# nfr24l_module.net
KiCad netlist of a schematic drawn in EAGLE
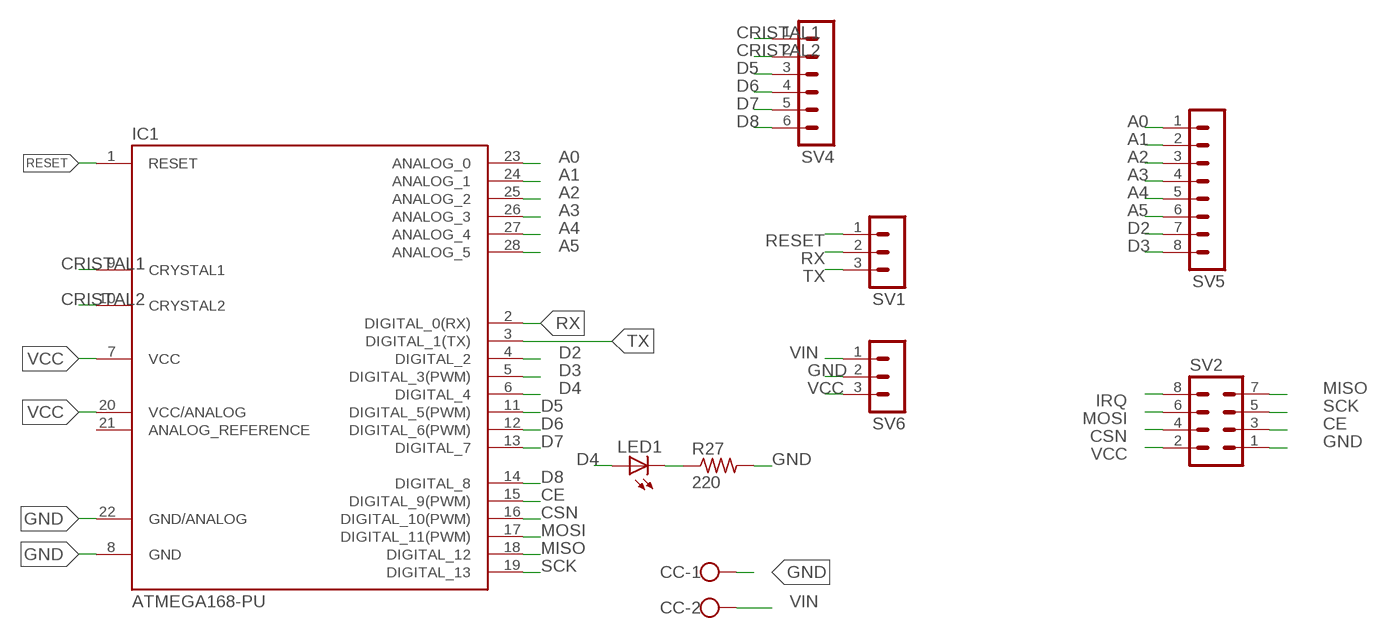
[diagram p0: schematic, sheet 1]

(export (version "E")
  (design (tool "Eeschema 10.0.6"))
  (components
    (comp (ref "CC")
      (value "W237-102")
      (footprint "eagle-import:W237-102")
      (fields (field (name "MPN") "237-102"))
      (libsource (lib "eagle-import") (part "W237-102"))
    )
    (comp (ref "IC1")
      (value "ATMEGA168-PU")
      (footprint "eagle-import:DIL28-3")
      (libsource (lib "eagle-import") (part "ATMEGA168-PU"))
    )
    (comp (ref "LED1")
      (value "LED3MM")
      (footprint "eagle-import:LED3MM")
      (libsource (lib "eagle-import") (part "LED3MM"))
    )
    (comp (ref "R27")
      (value "220")
      (footprint "eagle-import:0207_7")
      (libsource (lib "eagle-import") (part "R-US_0207/7"))
    )
    (comp (ref "SV1")
      (value "MA03-1")
      (footprint "eagle-import:MA03-1")
      (libsource (lib "eagle-import") (part "MA03-1"))
    )
    (comp (ref "SV2")
      (value "MA04-2")
      (footprint "eagle-import:MA04-2")
      (libsource (lib "eagle-import") (part "MA04-2"))
    )
    (comp (ref "SV4")
      (value "MA06-1")
      (footprint "eagle-import:MA06-1")
      (libsource (lib "eagle-import") (part "MA06-1"))
    )
    (comp (ref "SV5")
      (value "MA08-1")
      (footprint "eagle-import:MA08-1")
      (libsource (lib "eagle-import") (part "MA08-1"))
    )
    (comp (ref "SV6")
      (value "MA03-1")
      (footprint "eagle-import:MA03-1")
      (libsource (lib "eagle-import") (part "MA03-1"))
    )
  )
  (nets
    (net (code "1") (name "/A0") (class "Default")
      (node (ref "IC1") (pin "23") (pinfunction "ANALOG_0_23") (pintype "bidirectional"))
      (node (ref "SV5") (pin "1") (pinfunction "1_1") (pintype "passive"))
    )
    (net (code "2") (name "/A1") (class "Default")
      (node (ref "IC1") (pin "24") (pinfunction "ANALOG_1_24") (pintype "bidirectional"))
      (node (ref "SV5") (pin "2") (pinfunction "2_2") (pintype "passive"))
    )
    (net (code "3") (name "/A2") (class "Default")
      (node (ref "IC1") (pin "25") (pinfunction "ANALOG_2_25") (pintype "bidirectional"))
      (node (ref "SV5") (pin "3") (pinfunction "3_3") (pintype "passive"))
    )
    (net (code "4") (name "/A3") (class "Default")
      (node (ref "IC1") (pin "26") (pinfunction "ANALOG_3_26") (pintype "bidirectional"))
      (node (ref "SV5") (pin "4") (pinfunction "4_4") (pintype "passive"))
    )
    (net (code "5") (name "/A4") (class "Default")
      (node (ref "IC1") (pin "27") (pinfunction "ANALOG_4_27") (pintype "bidirectional"))
      (node (ref "SV5") (pin "5") (pinfunction "5_5") (pintype "passive"))
    )
    (net (code "6") (name "/A5") (class "Default")
      (node (ref "IC1") (pin "28") (pinfunction "ANALOG_5_28") (pintype "bidirectional"))
      (node (ref "SV5") (pin "6") (pinfunction "6_6") (pintype "passive"))
    )
    (net (code "7") (name "/CE") (class "Default")
      (node (ref "IC1") (pin "15") (pinfunction "DIGITAL_9(PWM)_15") (pintype "bidirectional"))
      (node (ref "SV2") (pin "3") (pinfunction "3_3") (pintype "passive"))
    )
    (net (code "8") (name "/CRISTAL1") (class "Default")
      (node (ref "IC1") (pin "9") (pinfunction "CRYSTAL1_9") (pintype "bidirectional"))
      (node (ref "SV4") (pin "1") (pinfunction "1_1") (pintype "passive"))
    )
    (net (code "9") (name "/CRISTAL2") (class "Default")
      (node (ref "IC1") (pin "10") (pinfunction "CRYSTAL2_10") (pintype "bidirectional"))
      (node (ref "SV4") (pin "2") (pinfunction "2_2") (pintype "passive"))
    )
    (net (code "10") (name "/CSN") (class "Default")
      (node (ref "IC1") (pin "16") (pinfunction "DIGITAL_10(PWM)_16") (pintype "bidirectional"))
      (node (ref "SV2") (pin "4") (pinfunction "4_4") (pintype "passive"))
    )
    (net (code "11") (name "/D2") (class "Default")
      (node (ref "IC1") (pin "4") (pinfunction "DIGITAL_2_4") (pintype "bidirectional"))
      (node (ref "SV5") (pin "7") (pinfunction "7_7") (pintype "passive"))
    )
    (net (code "12") (name "/D3") (class "Default")
      (node (ref "IC1") (pin "5") (pinfunction "DIGITAL_3(PWM)_5") (pintype "bidirectional"))
      (node (ref "SV5") (pin "8") (pinfunction "8_8") (pintype "passive"))
    )
    (net (code "13") (name "/D4") (class "Default")
      (node (ref "IC1") (pin "6") (pinfunction "DIGITAL_4_6") (pintype "bidirectional"))
      (node (ref "LED1") (pin "A") (pinfunction "A_A") (pintype "passive"))
    )
    (net (code "14") (name "/D5") (class "Default")
      (node (ref "IC1") (pin "11") (pinfunction "DIGITAL_5(PWM)_11") (pintype "bidirectional"))
      (node (ref "SV4") (pin "3") (pinfunction "3_3") (pintype "passive"))
    )
    (net (code "15") (name "/D6") (class "Default")
      (node (ref "IC1") (pin "12") (pinfunction "DIGITAL_6(PWM)_12") (pintype "bidirectional"))
      (node (ref "SV4") (pin "4") (pinfunction "4_4") (pintype "passive"))
    )
    (net (code "16") (name "/D7") (class "Default")
      (node (ref "IC1") (pin "13") (pinfunction "DIGITAL_7_13") (pintype "bidirectional"))
      (node (ref "SV4") (pin "5") (pinfunction "5_5") (pintype "passive"))
    )
    (net (code "17") (name "/D8") (class "Default")
      (node (ref "IC1") (pin "14") (pinfunction "DIGITAL_8_14") (pintype "bidirectional"))
      (node (ref "SV4") (pin "6") (pinfunction "6_6") (pintype "passive"))
    )
    (net (code "18") (name "/IRQ") (class "Default")
      (node (ref "SV2") (pin "8") (pinfunction "8_8") (pintype "passive"))
    )
    (net (code "19") (name "/MISO") (class "Default")
      (node (ref "IC1") (pin "18") (pinfunction "DIGITAL_12_18") (pintype "bidirectional"))
      (node (ref "SV2") (pin "7") (pinfunction "7_7") (pintype "passive"))
    )
    (net (code "20") (name "/MOSI") (class "Default")
      (node (ref "IC1") (pin "17") (pinfunction "DIGITAL_11(PWM)_17") (pintype "bidirectional"))
      (node (ref "SV2") (pin "6") (pinfunction "6_6") (pintype "passive"))
    )
    (net (code "21") (name "/SCK") (class "Default")
      (node (ref "IC1") (pin "19") (pinfunction "DIGITAL_13_19") (pintype "bidirectional"))
      (node (ref "SV2") (pin "5") (pinfunction "5_5") (pintype "passive"))
    )
    (net (code "22") (name "/VIN") (class "Default")
      (node (ref "CC") (pin "2") (pinfunction "KL_2") (pintype "passive"))
      (node (ref "SV6") (pin "1") (pinfunction "1_1") (pintype "passive"))
    )
    (net (code "23") (name "GND") (class "Default")
      (node (ref "CC") (pin "1") (pinfunction "KL_1") (pintype "passive"))
      (node (ref "IC1") (pin "22") (pinfunction "GND/ANALOG_22") (pintype "power_in"))
      (node (ref "IC1") (pin "8") (pinfunction "GND_8") (pintype "power_in"))
      (node (ref "R27") (pin "2") (pinfunction "2_2") (pintype "passive"))
      (node (ref "SV2") (pin "1") (pinfunction "1_1") (pintype "passive"))
      (node (ref "SV6") (pin "2") (pinfunction "2_2") (pintype "passive"))
    )
    (net (code "24") (name "Net-(LED1-C)") (class "Default")
      (node (ref "LED1") (pin "K") (pinfunction "C_K") (pintype "passive"))
      (node (ref "R27") (pin "1") (pinfunction "1_1") (pintype "passive"))
    )
    (net (code "25") (name "RESET") (class "Default")
      (node (ref "IC1") (pin "1") (pinfunction "RESET_1") (pintype "bidirectional"))
      (node (ref "SV1") (pin "1") (pinfunction "1_1") (pintype "passive"))
    )
    (net (code "26") (name "RX") (class "Default")
      (node (ref "IC1") (pin "2") (pinfunction "DIGITAL_0(RX)_2") (pintype "bidirectional"))
      (node (ref "SV1") (pin "2") (pinfunction "2_2") (pintype "passive"))
    )
    (net (code "27") (name "TX") (class "Default")
      (node (ref "IC1") (pin "3") (pinfunction "DIGITAL_1(TX)_3") (pintype "bidirectional"))
      (node (ref "SV1") (pin "3") (pinfunction "3_3") (pintype "passive"))
    )
    (net (code "28") (name "VCC") (class "Default")
      (node (ref "IC1") (pin "20") (pinfunction "VCC/ANALOG_20") (pintype "passive"))
      (node (ref "IC1") (pin "7") (pinfunction "VCC_7") (pintype "power_in"))
      (node (ref "SV2") (pin "2") (pinfunction "2_2") (pintype "passive"))
      (node (ref "SV6") (pin "3") (pinfunction "3_3") (pintype "passive"))
    )
    (net (code "29") (name "unconnected-(IC1-ANALOG_REFERENCE-Pad21)") (class "Default")
      (node (ref "IC1") (pin "21") (pinfunction "ANALOG_REFERENCE_21") (pintype "passive"))
    )
  )
)
